# LED-DRIVER.net
KiCad netlist of a schematic drawn in EAGLE
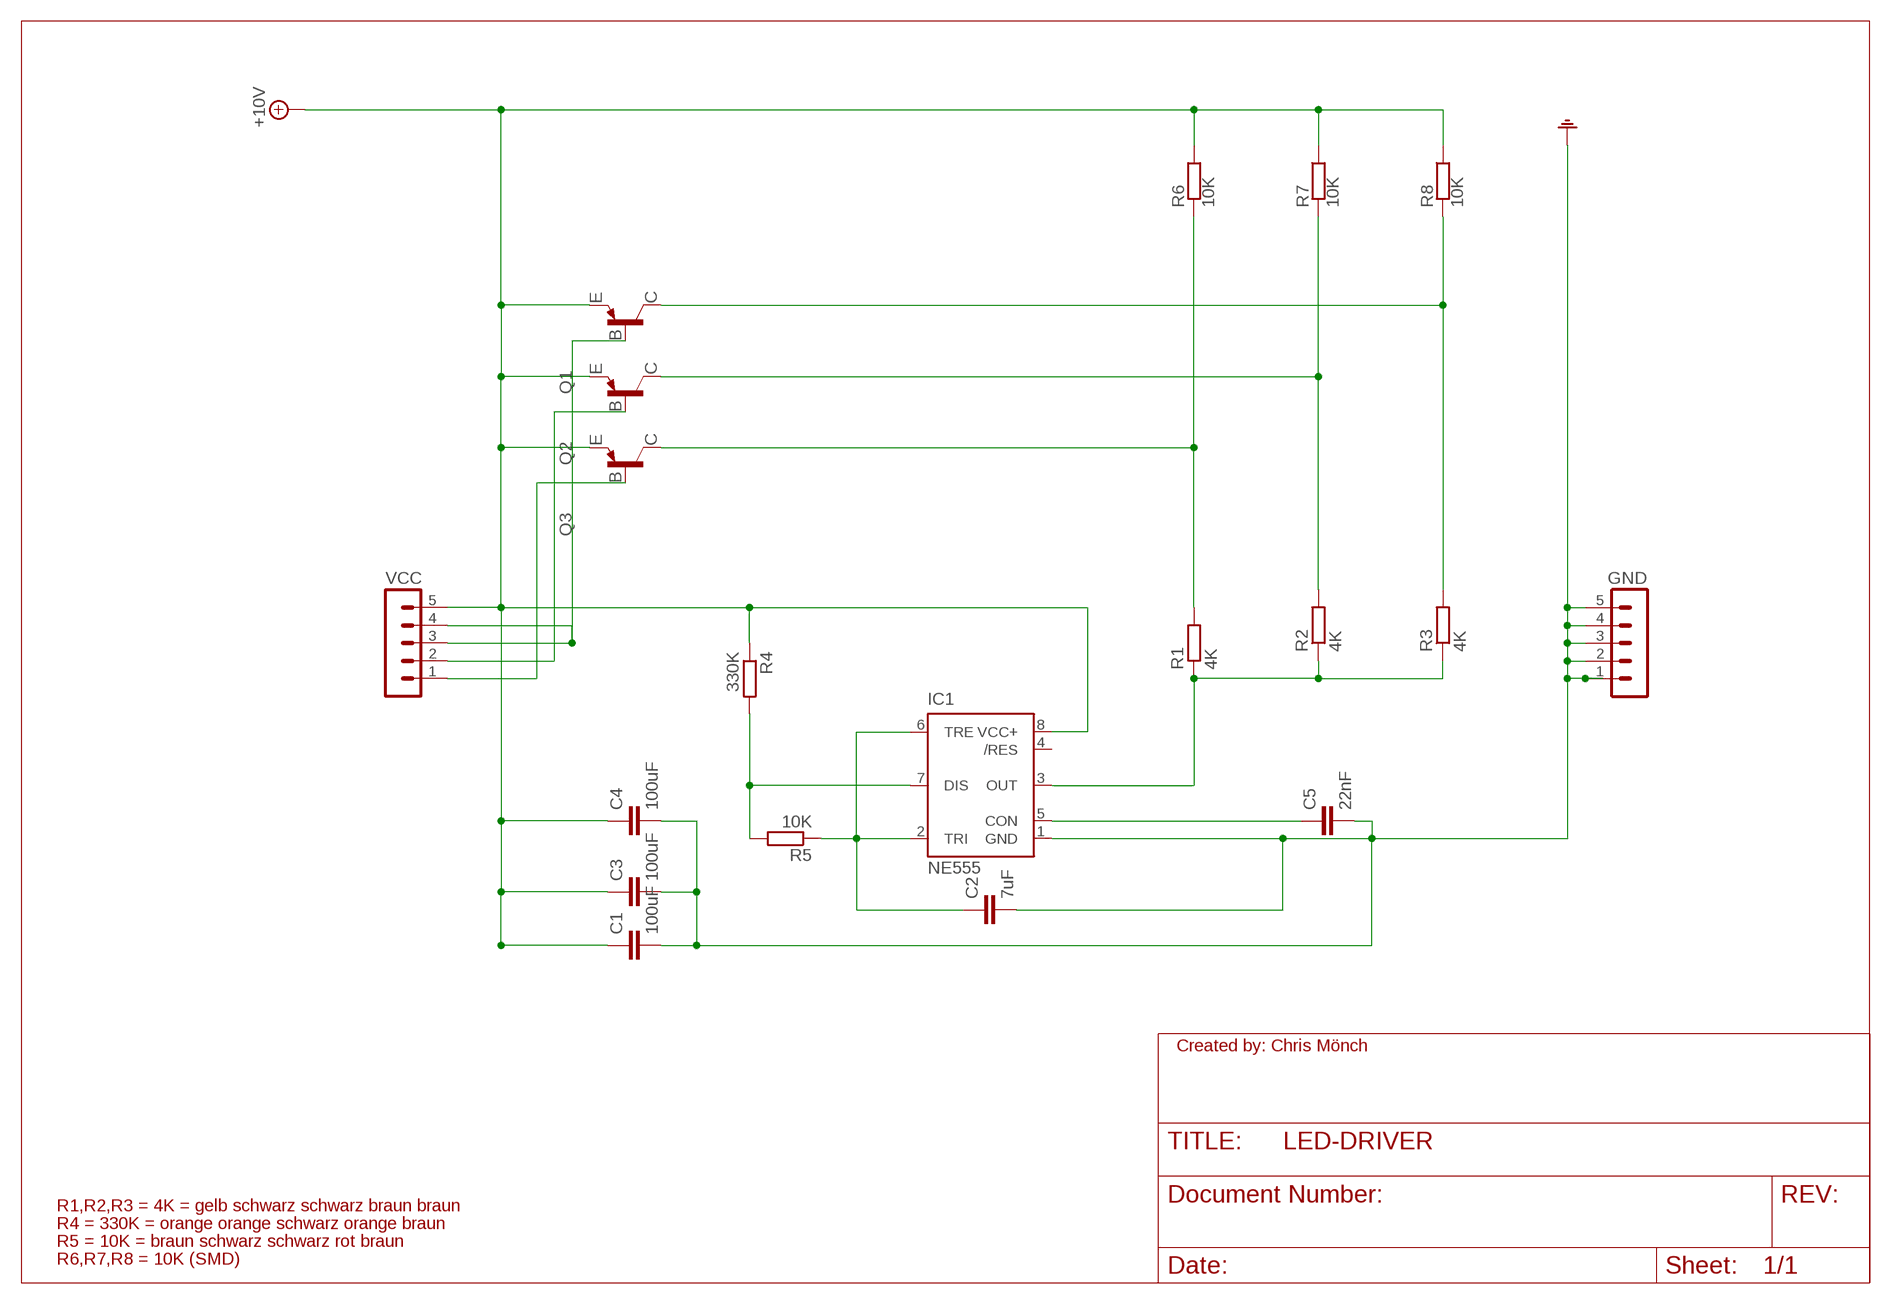
[diagram p0: schematic, sheet 1]

(export (version "E")
  (design (tool "Eeschema 10.0.6"))
  (components
    (comp (ref "C1")
      (value "100uF")
      (footprint "eagle-import:C2.5-3")
      (libsource (lib "eagle-import") (part "C2,5-3"))
    )
    (comp (ref "C2")
      (value "7uF")
      (footprint "eagle-import:C2.5-3")
      (libsource (lib "eagle-import") (part "C2,5-3"))
    )
    (comp (ref "C3")
      (value "100uF")
      (footprint "eagle-import:C2.5-3")
      (libsource (lib "eagle-import") (part "C2,5-3"))
    )
    (comp (ref "C4")
      (value "100uF")
      (footprint "eagle-import:C2.5-3")
      (libsource (lib "eagle-import") (part "C2,5-3"))
    )
    (comp (ref "C5")
      (value "22nF")
      (footprint "eagle-import:C2.5-3")
      (libsource (lib "eagle-import") (part "C2,5-3"))
    )
    (comp (ref "GND")
      (value "MA05-1")
      (footprint "eagle-import:MA05-1")
      (libsource (lib "eagle-import") (part "MA05-1"))
    )
    (comp (ref "IC1")
      (value "NE555")
      (footprint "eagle-import:DIL-08")
      (fields (field (name "MF") "Arrow Electronics") (field (name "MPN") "NE555N"))
      (libsource (lib "eagle-import") (part "NE555"))
    )
    (comp (ref "Q1")
      (value "2N3906MMBT")
      (footprint "eagle-import:SOT-23")
      (libsource (lib "eagle-import") (part "2N3906MMBT"))
    )
    (comp (ref "Q2")
      (value "2N3906MMBT")
      (footprint "eagle-import:SOT-23")
      (libsource (lib "eagle-import") (part "2N3906MMBT"))
    )
    (comp (ref "Q3")
      (value "2N3906MMBT")
      (footprint "eagle-import:SOT-23")
      (libsource (lib "eagle-import") (part "2N3906MMBT"))
    )
    (comp (ref "R1")
      (value "4K")
      (footprint "eagle-import:0204_5")
      (libsource (lib "eagle-import") (part "R-EU_0204/5"))
    )
    (comp (ref "R2")
      (value "4K")
      (footprint "eagle-import:0204_5")
      (libsource (lib "eagle-import") (part "R-EU_0204/5"))
    )
    (comp (ref "R3")
      (value "4K")
      (footprint "eagle-import:0204_5")
      (libsource (lib "eagle-import") (part "R-EU_0204/5"))
    )
    (comp (ref "R4")
      (value "330K")
      (footprint "eagle-import:0204_5")
      (libsource (lib "eagle-import") (part "R-EU_0204/5"))
    )
    (comp (ref "R5")
      (value "10K")
      (footprint "eagle-import:0204_5")
      (libsource (lib "eagle-import") (part "R-EU_0204/5"))
    )
    (comp (ref "R6")
      (value "10K")
      (footprint "eagle-import:SMS-0")
      (libsource (lib "eagle-import") (part "SMS-0"))
    )
    (comp (ref "R7")
      (value "10K")
      (footprint "eagle-import:SMS-0")
      (libsource (lib "eagle-import") (part "SMS-0"))
    )
    (comp (ref "R8")
      (value "10K")
      (footprint "eagle-import:SMS-0")
      (libsource (lib "eagle-import") (part "SMS-0"))
    )
    (comp (ref "U$1")
      (value "GND")
      (footprint "eagle-import:PWR")
      (libsource (lib "eagle-import") (part "GND"))
    )
    (comp (ref "VCC")
      (value "MA05-1")
      (footprint "eagle-import:MA05-1")
      (libsource (lib "eagle-import") (part "MA05-1"))
    )
  )
  (nets
    (net (code "1") (name "+10V") (class "Default")
      (node (ref "C1") (pin "1") (pinfunction "1_1") (pintype "passive"))
      (node (ref "C3") (pin "1") (pinfunction "1_1") (pintype "passive"))
      (node (ref "C4") (pin "1") (pinfunction "1_1") (pintype "passive"))
      (node (ref "IC1") (pin "8") (pinfunction "VCC+_8") (pintype "power_in"))
      (node (ref "Q1") (pin "2") (pinfunction "E_2") (pintype "passive"))
      (node (ref "Q2") (pin "2") (pinfunction "E_2") (pintype "passive"))
      (node (ref "Q3") (pin "2") (pinfunction "E_2") (pintype "passive"))
      (node (ref "R4") (pin "1") (pinfunction "1_1") (pintype "passive"))
      (node (ref "R6") (pin "1") (pinfunction "1_1") (pintype "passive"))
      (node (ref "R7") (pin "1") (pinfunction "1_1") (pintype "passive"))
      (node (ref "R8") (pin "1") (pinfunction "1_1") (pintype "passive"))
      (node (ref "VCC") (pin "5") (pinfunction "5_5") (pintype "passive"))
    )
    (net (code "2") (name "Net-(IC1-CON)") (class "Default")
      (node (ref "C5") (pin "1") (pinfunction "1_1") (pintype "passive"))
      (node (ref "IC1") (pin "5") (pinfunction "CON_5") (pintype "input"))
    )
    (net (code "3") (name "Net-(IC1-DIS)") (class "Default")
      (node (ref "IC1") (pin "7") (pinfunction "DIS_7") (pintype "input"))
      (node (ref "R4") (pin "2") (pinfunction "2_2") (pintype "passive"))
      (node (ref "R5") (pin "2") (pinfunction "2_2") (pintype "passive"))
    )
    (net (code "4") (name "Net-(IC1-GND)") (class "Default")
      (node (ref "C1") (pin "2") (pinfunction "2_2") (pintype "passive"))
      (node (ref "C2") (pin "2") (pinfunction "2_2") (pintype "passive"))
      (node (ref "C3") (pin "2") (pinfunction "2_2") (pintype "passive"))
      (node (ref "C4") (pin "2") (pinfunction "2_2") (pintype "passive"))
      (node (ref "C5") (pin "2") (pinfunction "2_2") (pintype "passive"))
      (node (ref "GND") (pin "1") (pinfunction "1_1") (pintype "passive"))
      (node (ref "GND") (pin "2") (pinfunction "2_2") (pintype "passive"))
      (node (ref "GND") (pin "3") (pinfunction "3_3") (pintype "passive"))
      (node (ref "GND") (pin "4") (pinfunction "4_4") (pintype "passive"))
      (node (ref "GND") (pin "5") (pinfunction "5_5") (pintype "passive"))
      (node (ref "IC1") (pin "1") (pinfunction "GND_1") (pintype "power_in"))
      (node (ref "U$1") (pin "P$1") (pinfunction "P$1_P$1") (pintype "power_in"))
    )
    (net (code "5") (name "Net-(IC1-OUT)") (class "Default")
      (node (ref "IC1") (pin "3") (pinfunction "OUT_3") (pintype "output"))
      (node (ref "R1") (pin "1") (pinfunction "1_1") (pintype "passive"))
      (node (ref "R2") (pin "1") (pinfunction "1_1") (pintype "passive"))
      (node (ref "R3") (pin "1") (pinfunction "1_1") (pintype "passive"))
    )
    (net (code "6") (name "Net-(IC1-TRE)") (class "Default")
      (node (ref "C2") (pin "1") (pinfunction "1_1") (pintype "passive"))
      (node (ref "IC1") (pin "2") (pinfunction "TRI_2") (pintype "input"))
      (node (ref "IC1") (pin "6") (pinfunction "TRE_6") (pintype "input"))
      (node (ref "R5") (pin "1") (pinfunction "1_1") (pintype "passive"))
    )
    (net (code "7") (name "Net-(Q1-B)") (class "Default")
      (node (ref "Q1") (pin "3") (pinfunction "B_3") (pintype "passive"))
      (node (ref "VCC") (pin "3") (pinfunction "3_3") (pintype "passive"))
      (node (ref "VCC") (pin "4") (pinfunction "4_4") (pintype "passive"))
    )
    (net (code "8") (name "Net-(Q1-C)") (class "Default")
      (node (ref "Q1") (pin "1") (pinfunction "C_1") (pintype "passive"))
      (node (ref "R3") (pin "2") (pinfunction "2_2") (pintype "passive"))
      (node (ref "R8") (pin "2") (pinfunction "2_2") (pintype "passive"))
    )
    (net (code "9") (name "Net-(Q2-B)") (class "Default")
      (node (ref "Q2") (pin "3") (pinfunction "B_3") (pintype "passive"))
      (node (ref "VCC") (pin "2") (pinfunction "2_2") (pintype "passive"))
    )
    (net (code "10") (name "Net-(Q2-C)") (class "Default")
      (node (ref "Q2") (pin "1") (pinfunction "C_1") (pintype "passive"))
      (node (ref "R2") (pin "2") (pinfunction "2_2") (pintype "passive"))
      (node (ref "R7") (pin "2") (pinfunction "2_2") (pintype "passive"))
    )
    (net (code "11") (name "Net-(Q3-B)") (class "Default")
      (node (ref "Q3") (pin "3") (pinfunction "B_3") (pintype "passive"))
      (node (ref "VCC") (pin "1") (pinfunction "1_1") (pintype "passive"))
    )
    (net (code "12") (name "Net-(Q3-C)") (class "Default")
      (node (ref "Q3") (pin "1") (pinfunction "C_1") (pintype "passive"))
      (node (ref "R1") (pin "2") (pinfunction "2_2") (pintype "passive"))
      (node (ref "R6") (pin "2") (pinfunction "2_2") (pintype "passive"))
    )
    (net (code "13") (name "unconnected-(IC1-{slash}RES-Pad4)") (class "Default")
      (node (ref "IC1") (pin "4") (pinfunction "/RES_4") (pintype "input"))
    )
  )
)
